# Basic_Mic_Preamp_6.net
KiCad netlist of a schematic drawn in EAGLE
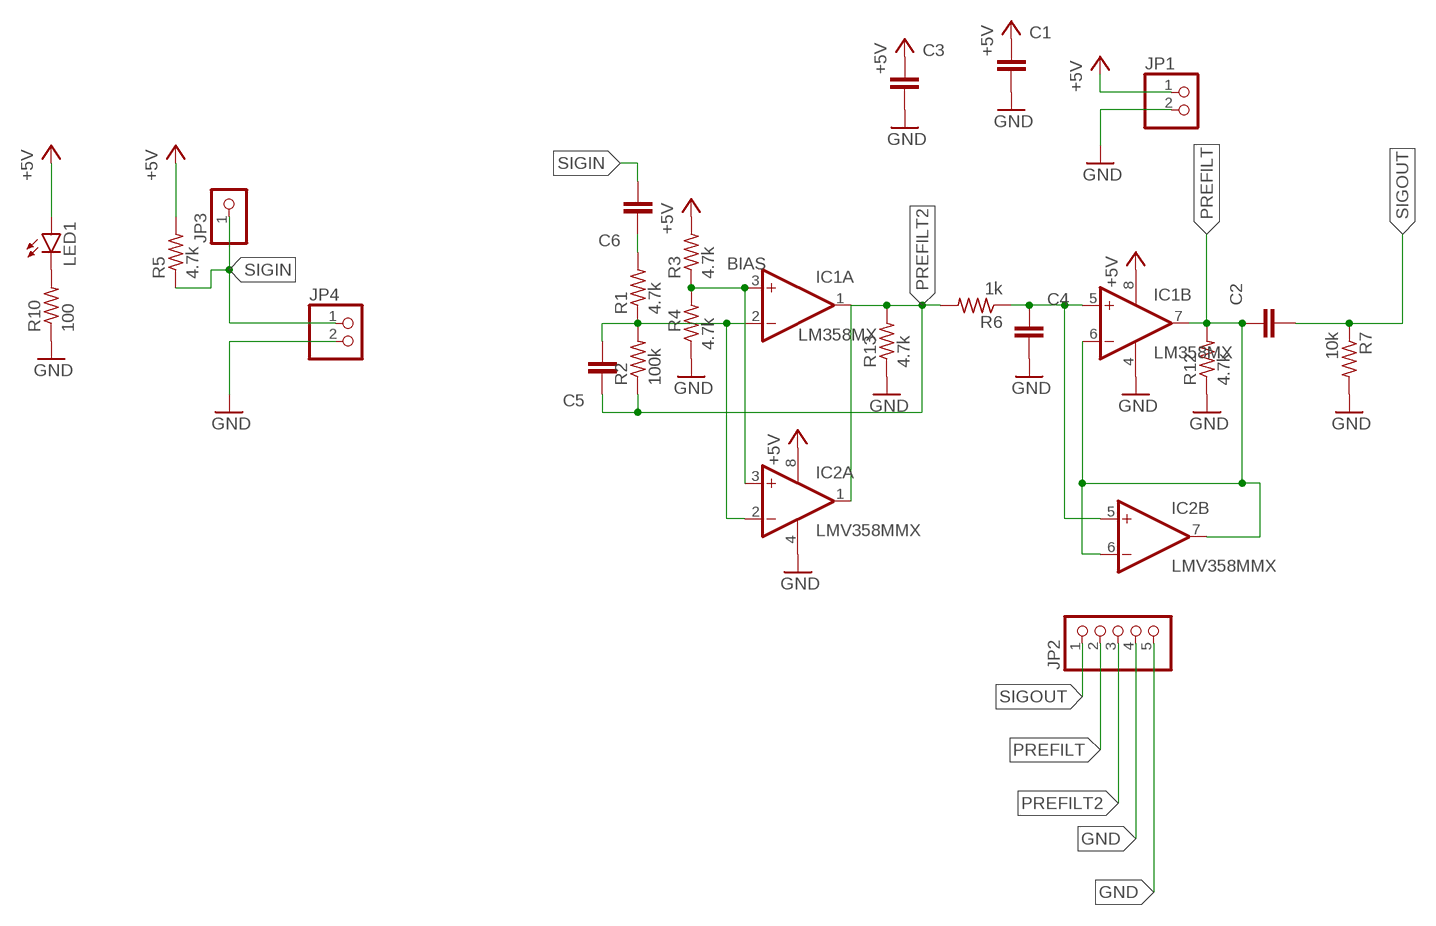
[diagram p0: schematic, sheet 1]

(export (version "E")
  (design (tool "Eeschema 10.0.6"))
  (components
    (comp (ref "C1")
      (value "10u")
      (footprint "eagle-import:C1206K")
      (libsource (lib "eagle-import") (part "C-EUC1206K"))
    )
    (comp (ref "C2")
      (value "1u")
      (footprint "eagle-import:C1206K")
      (libsource (lib "eagle-import") (part "C-EUC1206K"))
    )
    (comp (ref "C3")
      (value ".01u")
      (footprint "eagle-import:C1206K")
      (libsource (lib "eagle-import") (part "C-EUC1206K"))
    )
    (comp (ref "C4")
      (value ".01u")
      (footprint "eagle-import:C1206K")
      (libsource (lib "eagle-import") (part "C-EUC1206K"))
    )
    (comp (ref "C5")
      (value "500p")
      (footprint "eagle-import:C1206K")
      (libsource (lib "eagle-import") (part "C-EUC1206K"))
    )
    (comp (ref "C6")
      (value "1u")
      (footprint "eagle-import:C1206K")
      (libsource (lib "eagle-import") (part "C-EUC1206K"))
    )
    (comp (ref "IC1")
      (value "LM358MX")
      (footprint "eagle-import:SO08")
      (libsource (lib "eagle-import") (part "LM358MX"))
    )
    (comp (ref "IC2")
      (value "LMV358MMX")
      (footprint "eagle-import:MSOP08")
      (libsource (lib "eagle-import") (part "LMV358?MMX"))
    )
    (comp (ref "JP1")
      (value "PINHD-1X2/90")
      (footprint "eagle-import:1X02_90")
      (libsource (lib "eagle-import") (part "PINHD-1X2/90"))
    )
    (comp (ref "JP2")
      (value "PINHD-1X5/90")
      (footprint "eagle-import:1X05_90")
      (libsource (lib "eagle-import") (part "PINHD-1X5/90"))
    )
    (comp (ref "JP3")
      (value "PINHD-1X1")
      (footprint "eagle-import:1X01")
      (libsource (lib "eagle-import") (part "PINHD-1X1"))
    )
    (comp (ref "JP4")
      (value "PINHD-1X2/90")
      (footprint "eagle-import:1X02_90")
      (libsource (lib "eagle-import") (part "PINHD-1X2/90"))
    )
    (comp (ref "LED1")
      (value "LEDCHIPLED_1206")
      (footprint "eagle-import:CHIPLED_1206")
      (libsource (lib "eagle-import") (part "LEDCHIPLED_1206"))
    )
    (comp (ref "R1")
      (value "4.7k")
      (footprint "eagle-import:R1206W")
      (libsource (lib "eagle-import") (part "R-US_R1206W"))
    )
    (comp (ref "R2")
      (value "100k")
      (footprint "eagle-import:R1206W")
      (libsource (lib "eagle-import") (part "R-US_R1206W"))
    )
    (comp (ref "R3")
      (value "4.7k")
      (footprint "eagle-import:R1206W")
      (libsource (lib "eagle-import") (part "R-US_R1206W"))
    )
    (comp (ref "R4")
      (value "4.7k")
      (footprint "eagle-import:R1206W")
      (libsource (lib "eagle-import") (part "R-US_R1206W"))
    )
    (comp (ref "R5")
      (value "4.7k")
      (footprint "eagle-import:R1206W")
      (libsource (lib "eagle-import") (part "R-US_R1206W"))
    )
    (comp (ref "R6")
      (value "1k")
      (footprint "eagle-import:R1206W")
      (libsource (lib "eagle-import") (part "R-US_R1206W"))
    )
    (comp (ref "R7")
      (value "10k")
      (footprint "eagle-import:R1206W")
      (libsource (lib "eagle-import") (part "R-US_R1206W"))
    )
    (comp (ref "R10")
      (value "100")
      (footprint "eagle-import:R1206W")
      (libsource (lib "eagle-import") (part "R-US_R1206W"))
    )
    (comp (ref "R12")
      (value "4.7k")
      (footprint "eagle-import:R1206W")
      (libsource (lib "eagle-import") (part "R-US_R1206W"))
    )
    (comp (ref "R13")
      (value "4.7k")
      (footprint "eagle-import:R1206W")
      (libsource (lib "eagle-import") (part "R-US_R1206W"))
    )
  )
  (nets
    (net (code "1") (name "+5V") (class "Default")
      (node (ref "C1") (pin "1") (pinfunction "1_1") (pintype "passive"))
      (node (ref "C3") (pin "1") (pinfunction "1_1") (pintype "passive"))
      (node (ref "IC1") (pin "8") (pinfunction "V+_8") (pintype "power_in"))
      (node (ref "IC2") (pin "8") (pinfunction "V+_8") (pintype "power_in"))
      (node (ref "JP1") (pin "1") (pinfunction "1_1") (pintype "passive"))
      (node (ref "LED1") (pin "A") (pinfunction "A_A") (pintype "passive"))
      (node (ref "R3") (pin "2") (pinfunction "2_2") (pintype "passive"))
      (node (ref "R5") (pin "2") (pinfunction "2_2") (pintype "passive"))
    )
    (net (code "2") (name "/BIAS") (class "Default")
      (node (ref "IC1") (pin "3") (pinfunction "+IN_3") (pintype "input"))
      (node (ref "IC2") (pin "3") (pinfunction "+IN_3") (pintype "input"))
      (node (ref "R3") (pin "1") (pinfunction "1_1") (pintype "passive"))
      (node (ref "R4") (pin "2") (pinfunction "2_2") (pintype "passive"))
    )
    (net (code "3") (name "GND") (class "Default")
      (node (ref "C1") (pin "2") (pinfunction "2_2") (pintype "passive"))
      (node (ref "C3") (pin "2") (pinfunction "2_2") (pintype "passive"))
      (node (ref "C4") (pin "2") (pinfunction "2_2") (pintype "passive"))
      (node (ref "IC1") (pin "4") (pinfunction "V-_4") (pintype "power_in"))
      (node (ref "IC2") (pin "4") (pinfunction "V-_4") (pintype "power_in"))
      (node (ref "JP1") (pin "2") (pinfunction "2_2") (pintype "passive"))
      (node (ref "JP2") (pin "4") (pinfunction "4_4") (pintype "passive"))
      (node (ref "JP2") (pin "5") (pinfunction "5_5") (pintype "passive"))
      (node (ref "JP4") (pin "2") (pinfunction "2_2") (pintype "passive"))
      (node (ref "R10") (pin "1") (pinfunction "1_1") (pintype "passive"))
      (node (ref "R12") (pin "1") (pinfunction "1_1") (pintype "passive"))
      (node (ref "R13") (pin "1") (pinfunction "1_1") (pintype "passive"))
      (node (ref "R4") (pin "1") (pinfunction "1_1") (pintype "passive"))
      (node (ref "R7") (pin "2") (pinfunction "2_2") (pintype "passive"))
    )
    (net (code "4") (name "Net-(C6-Pad1)") (class "Default")
      (node (ref "C6") (pin "1") (pinfunction "1_1") (pintype "passive"))
      (node (ref "R1") (pin "2") (pinfunction "2_2") (pintype "passive"))
    )
    (net (code "5") (name "Net-(IC1A--IN)") (class "Default")
      (node (ref "C5") (pin "2") (pinfunction "2_2") (pintype "passive"))
      (node (ref "IC1") (pin "2") (pinfunction "-IN_2") (pintype "input"))
      (node (ref "IC2") (pin "2") (pinfunction "-IN_2") (pintype "input"))
      (node (ref "R1") (pin "1") (pinfunction "1_1") (pintype "passive"))
      (node (ref "R2") (pin "2") (pinfunction "2_2") (pintype "passive"))
    )
    (net (code "6") (name "Net-(IC1B-+IN)") (class "Default")
      (node (ref "C4") (pin "1") (pinfunction "1_1") (pintype "passive"))
      (node (ref "IC1") (pin "5") (pinfunction "+IN_5") (pintype "input"))
      (node (ref "IC2") (pin "5") (pinfunction "+IN_5") (pintype "input"))
      (node (ref "R6") (pin "1") (pinfunction "1_1") (pintype "passive"))
    )
    (net (code "7") (name "Net-(LED1-PadC)") (class "Default")
      (node (ref "LED1") (pin "C") (pinfunction "C_C") (pintype "passive"))
      (node (ref "R10") (pin "2") (pinfunction "2_2") (pintype "passive"))
    )
    (net (code "8") (name "PREFILT") (class "Default")
      (node (ref "C2") (pin "1") (pinfunction "1_1") (pintype "passive"))
      (node (ref "IC1") (pin "6") (pinfunction "-IN_6") (pintype "input"))
      (node (ref "IC1") (pin "7") (pinfunction "OUT_7") (pintype "output"))
      (node (ref "IC2") (pin "6") (pinfunction "-IN_6") (pintype "input"))
      (node (ref "IC2") (pin "7") (pinfunction "OUT_7") (pintype "output"))
      (node (ref "JP2") (pin "2") (pinfunction "2_2") (pintype "passive"))
      (node (ref "R12") (pin "2") (pinfunction "2_2") (pintype "passive"))
    )
    (net (code "9") (name "PREFILT2") (class "Default")
      (node (ref "C5") (pin "1") (pinfunction "1_1") (pintype "passive"))
      (node (ref "IC1") (pin "1") (pinfunction "OUT_1") (pintype "output"))
      (node (ref "IC2") (pin "1") (pinfunction "OUT_1") (pintype "output"))
      (node (ref "JP2") (pin "3") (pinfunction "3_3") (pintype "passive"))
      (node (ref "R13") (pin "2") (pinfunction "2_2") (pintype "passive"))
      (node (ref "R2") (pin "1") (pinfunction "1_1") (pintype "passive"))
      (node (ref "R6") (pin "2") (pinfunction "2_2") (pintype "passive"))
    )
    (net (code "10") (name "SIGIN") (class "Default")
      (node (ref "C6") (pin "2") (pinfunction "2_2") (pintype "passive"))
      (node (ref "JP3") (pin "1") (pinfunction "1_1") (pintype "passive"))
      (node (ref "JP4") (pin "1") (pinfunction "1_1") (pintype "passive"))
      (node (ref "R5") (pin "1") (pinfunction "1_1") (pintype "passive"))
    )
    (net (code "11") (name "SIGOUT") (class "Default")
      (node (ref "C2") (pin "2") (pinfunction "2_2") (pintype "passive"))
      (node (ref "JP2") (pin "1") (pinfunction "1_1") (pintype "passive"))
      (node (ref "R7") (pin "1") (pinfunction "1_1") (pintype "passive"))
    )
  )
)
